# eLight_SD1006.net
KiCad netlist of a schematic drawn in EasyEDA Pro
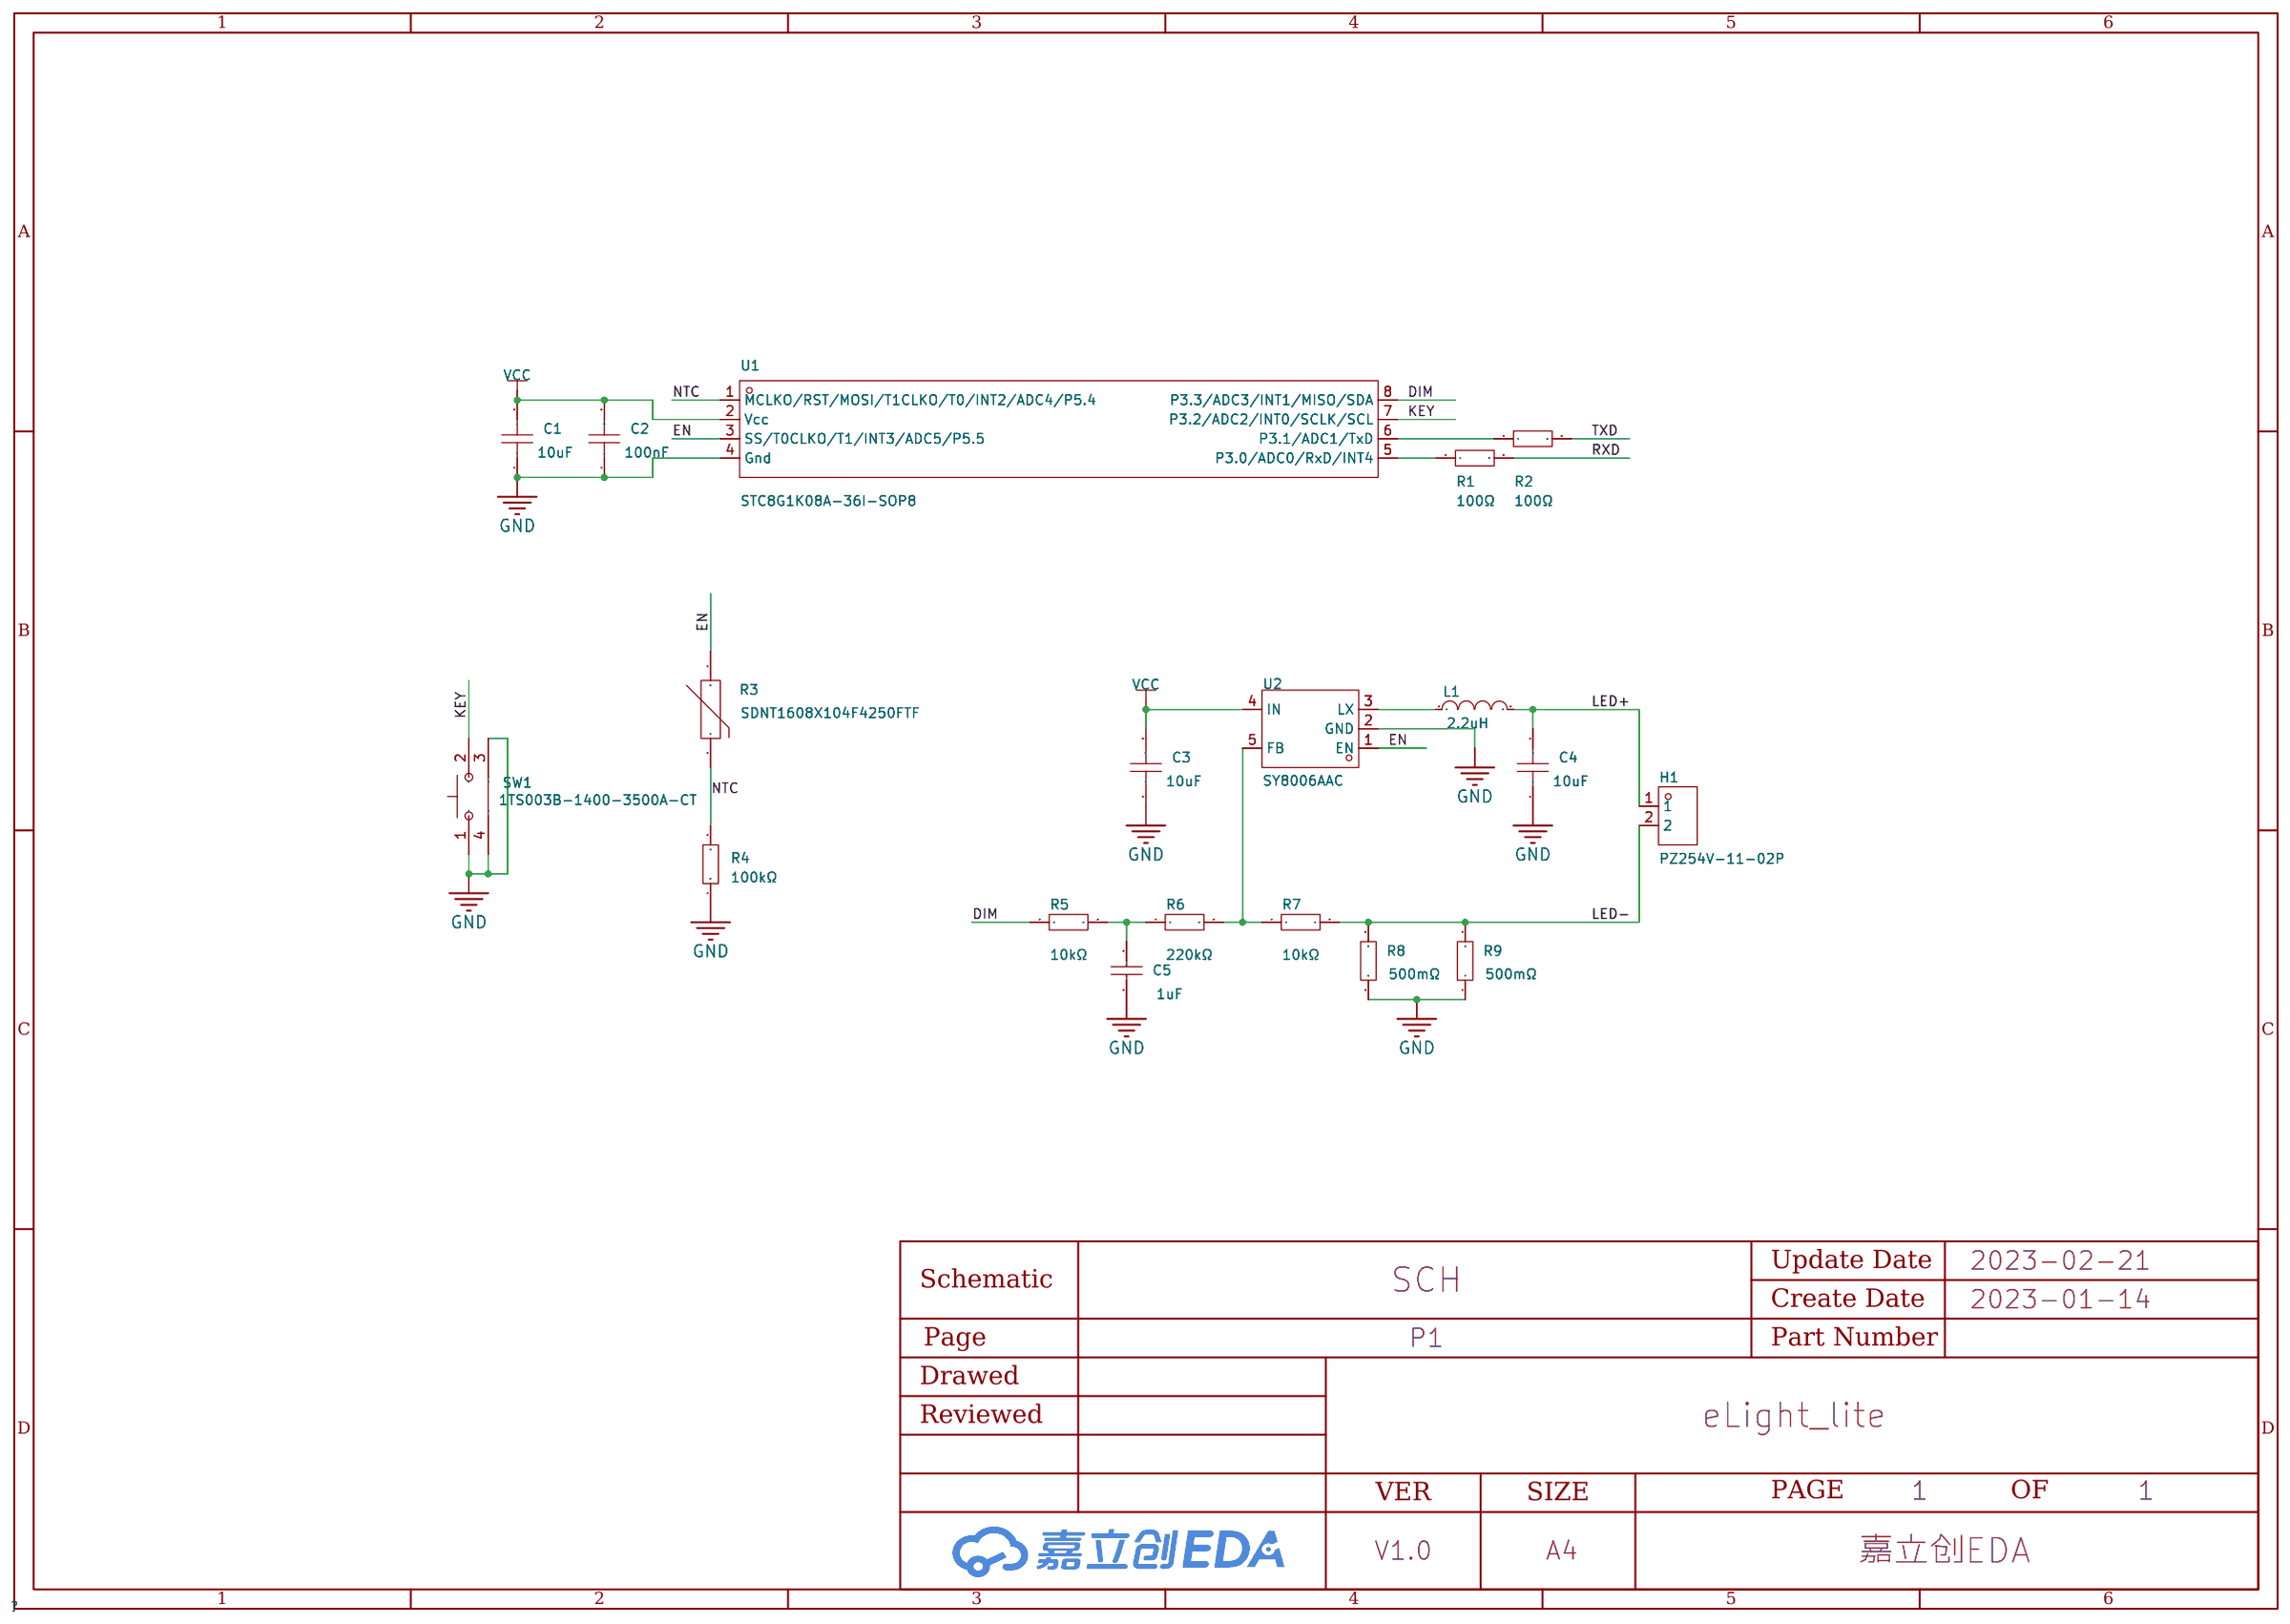
[diagram p0: schematic sheet]

(export (version "E")
  (design (tool "Eeschema 10.0.6"))
  (components
    (comp (ref "C1")
      (value "10uF")
      (footprint "easyedapro:C0603")
      (description "容值:10uF;精度:±10%;额定电压:10V;材质(温度系数):X5R;")
      (fields
        (field (name "Manufacturer Part") "CL10A106KP8NNNC")
        (field (name "Manufacturer") "SAMSUNG(三星)")
      )
      (libsource (lib "easyedapro") (part "CL10A106KP8NNNC"))
    )
    (comp (ref "C2")
      (value "100nF")
      (footprint "easyedapro:C0603")
      (description "容值:100nF;精度:±10%;额定电压:50V;材质(温度系数):X7R;")
      (fields
        (field (name "Manufacturer Part") "CC0603KRX7R9BB104")
        (field (name "Manufacturer") "YAGEO(国巨)")
      )
      (libsource (lib "easyedapro") (part "CC0603KRX7R9BB104"))
    )
    (comp (ref "C3")
      (value "10uF")
      (footprint "easyedapro:C0603")
      (description "容值:10uF;精度:±10%;额定电压:10V;材质(温度系数):X5R;")
      (fields
        (field (name "Manufacturer Part") "CL10A106KP8NNNC")
        (field (name "Manufacturer") "SAMSUNG(三星)")
      )
      (libsource (lib "easyedapro") (part "CL10A106KP8NNNC"))
    )
    (comp (ref "C4")
      (value "10uF")
      (footprint "easyedapro:C0603")
      (description "容值:10uF;精度:±10%;额定电压:10V;材质(温度系数):X5R;")
      (fields
        (field (name "Manufacturer Part") "CL10A106KP8NNNC")
        (field (name "Manufacturer") "SAMSUNG(三星)")
      )
      (libsource (lib "easyedapro") (part "CL10A106KP8NNNC"))
    )
    (comp (ref "C5")
      (value "1uF")
      (footprint "easyedapro:C0603")
      (description "容值:1uF;精度:±10%;额定电压:50V;材质(温度系数):X5R;")
      (fields
        (field (name "Manufacturer Part") "CL10A105KB8NNNC")
        (field (name "Manufacturer") "SAMSUNG(三星)")
      )
      (libsource (lib "easyedapro") (part "CL10A105KB8NNNC"))
    )
    (comp (ref "H1")
      (value "PZ254V-11-02P")
      (footprint "easyedapro:HDR-TH_2P-P2.54-V-M")
      (fields (field (name "Manufacturer") "XFCN(兴飞)"))
      (libsource (lib "easyedapro") (part "PZ254V-11-02P"))
    )
    (comp (ref "L1")
      (value "2.2uH")
      (footprint "easyedapro:IND-SMD_L4.5-W4.0-1")
      (description "电感值:2.2uH;精度:±20%;额定电流:3A;直流电阻(DCR):52mΩ;")
      (fields (field (name "Manufacturer Part") "SWPA4020S2R2MT") (field (name "Manufacturer") "Sunlord(顺络)"))
      (libsource (lib "easyedapro") (part "MCS0420-2R2MN2"))
    )
    (comp (ref "R1")
      (value "100Ω")
      (footprint "easyedapro:R0603")
      (description "电阻类型:厚膜电阻;阻值:100Ω;精度:±1%;功率:100mW;温度系数:±200ppm/°C;最大工作电压:75V;工作温度范围:-55°C~+155°C;")
      (fields
        (field (name "Manufacturer Part") "0603WAF1000T5E")
        (field (name "Manufacturer") "UNI-ROYAL(厚声)")
      )
      (libsource (lib "easyedapro") (part "0603WAF1000T5E"))
    )
    (comp (ref "R2")
      (value "100Ω")
      (footprint "easyedapro:R0603")
      (description "电阻类型:厚膜电阻;阻值:100Ω;精度:±1%;功率:100mW;温度系数:±200ppm/°C;最大工作电压:75V;工作温度范围:-55°C~+155°C;")
      (fields
        (field (name "Manufacturer Part") "0603WAF1000T5E")
        (field (name "Manufacturer") "UNI-ROYAL(厚声)")
      )
      (libsource (lib "easyedapro") (part "0603WAF1000T5E"))
    )
    (comp (ref "R3")
      (value "SDNT1608X104F4250FTF")
      (footprint "easyedapro:R0603")
      (fields (field (name "Manufacturer") "Sunlord(顺络)") (field (name "Power") "100mW"))
      (libsource (lib "easyedapro") (part "SDNT1608X103F3950FTF"))
    )
    (comp (ref "R4")
      (value "100kΩ")
      (footprint "easyedapro:R0603")
      (description "电阻类型:厚膜电阻;阻值:10kΩ;精度:±1%;功率:100mW;温度系数:±100ppm/°C;最大工作电压:75V;工作温度范围:-55°C~+155°C;")
      (fields
        (field (name "Manufacturer Part") "0603WAF1003T5E")
        (field (name "Manufacturer") "UNI-ROYAL(厚声)")
      )
      (libsource (lib "easyedapro") (part "0603WAF1002T5E"))
    )
    (comp (ref "R5")
      (value "10kΩ")
      (footprint "easyedapro:R0603")
      (description "电阻类型:厚膜电阻;阻值:100kΩ;精度:±1%;功率:100mW;温度系数:±100ppm/°C;最大工作电压:75V;工作温度范围:-55°C~+155°C;")
      (fields
        (field (name "Manufacturer Part") "0603WAF1002T5E")
        (field (name "Manufacturer") "UNI-ROYAL(厚声)")
      )
      (libsource (lib "easyedapro") (part "0603WAF1003T5E"))
    )
    (comp (ref "R6")
      (value "220kΩ")
      (footprint "easyedapro:R0603")
      (description "电阻类型:厚膜电阻;阻值:100kΩ;精度:±1%;功率:100mW;温度系数:±100ppm/°C;最大工作电压:75V;工作温度范围:-55°C~+155°C;")
      (fields
        (field (name "Manufacturer Part") "0603WAF2203T5E")
        (field (name "Manufacturer") "UNI-ROYAL(厚声)")
      )
      (libsource (lib "easyedapro") (part "0603WAF1003T5E"))
    )
    (comp (ref "R7")
      (value "10kΩ")
      (footprint "easyedapro:R0603")
      (description "电阻类型:厚膜电阻;阻值:100kΩ;精度:±1%;功率:100mW;温度系数:±100ppm/°C;最大工作电压:75V;工作温度范围:-55°C~+155°C;")
      (fields
        (field (name "Manufacturer Part") "0603WAF1002T5E")
        (field (name "Manufacturer") "UNI-ROYAL(厚声)")
      )
      (libsource (lib "easyedapro") (part "0603WAF1003T5E"))
    )
    (comp (ref "R8")
      (value "500mΩ")
      (footprint "easyedapro:R0805")
      (description "电阻类型:厚膜电阻;阻值:500mΩ;精度:±1%;功率:125mW;温度系数:±800ppm/℃;最大工作电压:150V;工作温度范围:-55℃~+155℃;")
      (fields
        (field (name "Manufacturer Part") "0805W8F500LT5E")
        (field (name "Manufacturer") "UNI-ROYAL(厚声)")
      )
      (libsource (lib "easyedapro") (part "0805W8F510LT5E"))
    )
    (comp (ref "R9")
      (value "500mΩ")
      (footprint "easyedapro:R0805")
      (description "电阻类型:厚膜电阻;阻值:510mΩ;精度:±1%;功率:125mW;温度系数:±800ppm/°C;最大工作电压:150V;工作温度范围:-55°C~+155°C;")
      (fields
        (field (name "Manufacturer Part") "0805W8F500LT5E")
        (field (name "Manufacturer") "UNI-ROYAL(厚声)")
      )
      (libsource (lib "easyedapro") (part "0805W8F510LT5E"))
    )
    (comp (ref "SW1")
      (value "1TS003B-1400-3500A-CT")
      (footprint "easyedapro:KEY-SMD_1TS003B")
      (fields (field (name "Manufacturer") "HYP(鸿源精密)"))
      (libsource (lib "easyedapro") (part "1TS003B-1400-3500A"))
    )
    (comp (ref "U1")
      (value "STC8G1K08A-36I-SOP8")
      (footprint "easyedapro:SOP-8_L5.0-W4.0-P1.27-LS6.0-BL")
      (fields (field (name "Manufacturer") "STC(宏晶)"))
      (libsource (lib "easyedapro") (part "STC8G1K08A-36I-SOP8"))
    )
    (comp (ref "U2")
      (value "SY8006AAC")
      (footprint "easyedapro:SOT-23-5_L3.0-W1.6-P0.95-LS2.8-BR")
      (fields (field (name "Manufacturer") "silergy(矽力杰)"))
      (libsource (lib "easyedapro") (part "SY8006AAC"))
    )
  )
  (nets
    (net (code "1") (name "/DIM") (class "Default")
      (node (ref "R5") (pin "1") (pinfunction "1_1") (pintype "input"))
      (node (ref "U1") (pin "8") (pinfunction "P3.3/ADC3/INT1/MISO/SDA_8") (pintype "input"))
    )
    (net (code "2") (name "/EN") (class "Default")
      (node (ref "R3") (pin "2") (pinfunction "2_2") (pintype "input"))
      (node (ref "U1") (pin "3") (pinfunction "SS/T0CLKO/T1/INT3/ADC5/P5.5_3") (pintype "input"))
      (node (ref "U2") (pin "1") (pinfunction "EN_1") (pintype "input"))
    )
    (net (code "3") (name "/KEY") (class "Default")
      (node (ref "SW1") (pin "2") (pinfunction "2_2") (pintype "input"))
      (node (ref "U1") (pin "7") (pinfunction "P3.2/ADC2/INT0/SCLK/SCL_7") (pintype "input"))
    )
    (net (code "4") (name "/LED+") (class "Default")
      (node (ref "C4") (pin "2") (pinfunction "2_2") (pintype "input"))
      (node (ref "H1") (pin "1") (pinfunction "1_1") (pintype "input"))
      (node (ref "L1") (pin "2") (pinfunction "2_2") (pintype "input"))
    )
    (net (code "5") (name "/LED-") (class "Default")
      (node (ref "H1") (pin "2") (pinfunction "2_2") (pintype "input"))
      (node (ref "R7") (pin "2") (pinfunction "2_2") (pintype "input"))
      (node (ref "R8") (pin "2") (pinfunction "2_2") (pintype "input"))
      (node (ref "R9") (pin "2") (pinfunction "2_2") (pintype "input"))
    )
    (net (code "6") (name "/NTC") (class "Default")
      (node (ref "R3") (pin "1") (pinfunction "1_1") (pintype "input"))
      (node (ref "R4") (pin "2") (pinfunction "2_2") (pintype "input"))
      (node (ref "U1") (pin "1") (pinfunction "MCLKO/RST/MOSI/T1CLKO/T0/INT2/ADC4/P5.4_1") (pintype "input"))
    )
    (net (code "7") (name "/RXD") (class "Default")
      (node (ref "R1") (pin "2") (pinfunction "2_2") (pintype "input"))
    )
    (net (code "8") (name "/TXD") (class "Default")
      (node (ref "R2") (pin "2") (pinfunction "2_2") (pintype "input"))
    )
    (net (code "9") (name "GND") (class "Default")
      (node (ref "C1") (pin "1") (pinfunction "1_1") (pintype "input"))
      (node (ref "C2") (pin "1") (pinfunction "1_1") (pintype "input"))
      (node (ref "C3") (pin "1") (pinfunction "1_1") (pintype "input"))
      (node (ref "C4") (pin "1") (pinfunction "1_1") (pintype "input"))
      (node (ref "C5") (pin "1") (pinfunction "1_1") (pintype "input"))
      (node (ref "R4") (pin "1") (pinfunction "1_1") (pintype "input"))
      (node (ref "R8") (pin "1") (pinfunction "1_1") (pintype "input"))
      (node (ref "R9") (pin "1") (pinfunction "1_1") (pintype "input"))
      (node (ref "SW1") (pin "1") (pinfunction "1_1") (pintype "input"))
      (node (ref "SW1") (pin "3") (pinfunction "3_3") (pintype "input"))
      (node (ref "SW1") (pin "4") (pinfunction "4_4") (pintype "input"))
      (node (ref "U1") (pin "4") (pinfunction "Gnd_4") (pintype "input"))
      (node (ref "U2") (pin "2") (pinfunction "GND_2") (pintype "input"))
    )
    (net (code "10") (name "Net-(C5-Pad2)") (class "Default")
      (node (ref "C5") (pin "2") (pinfunction "2_2") (pintype "input"))
      (node (ref "R5") (pin "2") (pinfunction "2_2") (pintype "input"))
      (node (ref "R6") (pin "1") (pinfunction "1_1") (pintype "input"))
    )
    (net (code "11") (name "Net-(U1-P3.0{slash}ADC0{slash}RxD{slash}INT4)") (class "Default")
      (node (ref "R1") (pin "1") (pinfunction "1_1") (pintype "input"))
      (node (ref "U1") (pin "5") (pinfunction "P3.0/ADC0/RxD/INT4_5") (pintype "input"))
    )
    (net (code "12") (name "Net-(U1-P3.1{slash}ADC1{slash}TxD)") (class "Default")
      (node (ref "R2") (pin "1") (pinfunction "1_1") (pintype "input"))
      (node (ref "U1") (pin "6") (pinfunction "P3.1/ADC1/TxD_6") (pintype "input"))
    )
    (net (code "13") (name "Net-(U2-FB)") (class "Default")
      (node (ref "R6") (pin "2") (pinfunction "2_2") (pintype "input"))
      (node (ref "R7") (pin "1") (pinfunction "1_1") (pintype "input"))
      (node (ref "U2") (pin "5") (pinfunction "FB_5") (pintype "input"))
    )
    (net (code "14") (name "Net-(U2-LX)") (class "Default")
      (node (ref "L1") (pin "1") (pinfunction "1_1") (pintype "input"))
      (node (ref "U2") (pin "3") (pinfunction "LX_3") (pintype "input"))
    )
    (net (code "15") (name "VCC") (class "Default")
      (node (ref "C1") (pin "2") (pinfunction "2_2") (pintype "input"))
      (node (ref "C2") (pin "2") (pinfunction "2_2") (pintype "input"))
      (node (ref "C3") (pin "2") (pinfunction "2_2") (pintype "input"))
      (node (ref "U1") (pin "2") (pinfunction "Vcc_2") (pintype "input"))
      (node (ref "U2") (pin "4") (pinfunction "IN_4") (pintype "input"))
    )
  )
)
